# power.net
KiCad netlist of a schematic drawn in Altium Designer
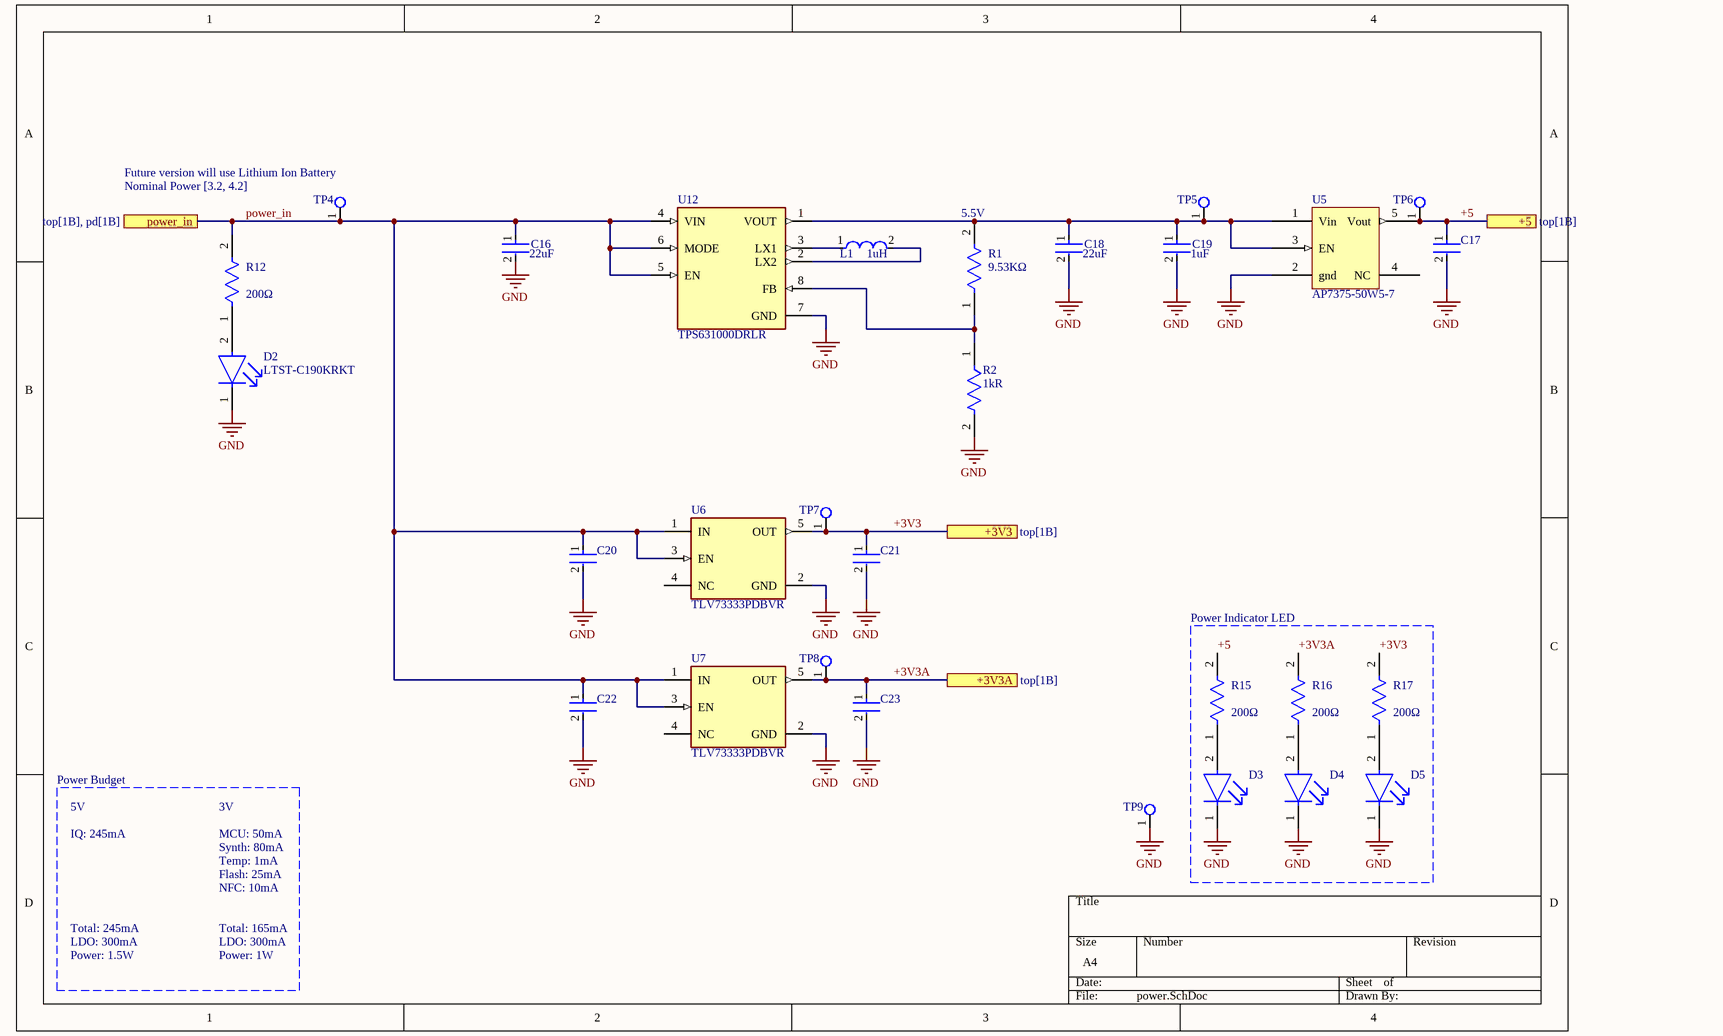
[diagram p0: power.SchDoc]

(export (version "E")
  (design (tool "Eeschema 10.0.6"))
  (components
    (comp (ref "C16")
      (value "GRM188R61A226ME15D")
      (footprint "FP-GRM188-0_2-IPC_C")
      (description "Chip Multilayer Ceramic Capacitors for General Purpose, 0603, 22uF, X5R, 15%, 20%, 10V")
      (fields (field (name "TOLERANCE") "20%") (field (name "CAPACITANCE") "22uF"))
      (libsource (lib "Altium Content Vault") (part "11868f565c42a9108669ba33697ecf6"))
    )
    (comp (ref "C17")
      (value "GRM155R61A106ME11D")
      (footprint "FP-GRM155-0_2-IPC_A")
      (description "Chip Multilayer Ceramic Capacitors for General Purpose, 0402, 10uF, X5R, 15%, 20%, 10V")
      (libsource (lib "Altium Content Vault") (part "b4654b650e69147ec39a6b967a45e02"))
    )
    (comp (ref "C18")
      (value "GRM188R61A226ME15D")
      (footprint "FP-GRM188-0_2-IPC_C")
      (description "Chip Multilayer Ceramic Capacitors for General Purpose, 0603, 22uF, X5R, 15%, 20%, 10V")
      (fields (field (name "TOLERANCE") "20%") (field (name "CAPACITANCE") "22uF"))
      (libsource (lib "Altium Content Vault") (part "11868f565c42a9108669ba33697ecf6"))
    )
    (comp (ref "C19")
      (value "CL10B105KP8NNNC")
      (footprint "FP-CL10-IPC_C")
      (description "Cap Ceramic 1uF 10V X7R ±10% Pad SMD 0603 +125°C T/R")
      (fields (field (name "CAPACITANCE") "1uF") (field (name "TOLERANCE") "10%"))
      (libsource (lib "Altium Content Vault") (part "b4654b650e69147ec39a6b967a45e02"))
    )
    (comp (ref "C20")
      (value "GRM155R61A106ME11D")
      (footprint "FP-GRM155-0_2-IPC_A")
      (description "Chip Multilayer Ceramic Capacitors for General Purpose, 0402, 10uF, X5R, 15%, 20%, 10V")
      (libsource (lib "Altium Content Vault") (part "b4654b650e69147ec39a6b967a45e02"))
    )
    (comp (ref "C21")
      (value "GRM155R61A106ME11D")
      (footprint "FP-GRM155-0_2-IPC_A")
      (description "Chip Multilayer Ceramic Capacitors for General Purpose, 0402, 10uF, X5R, 15%, 20%, 10V")
      (libsource (lib "Altium Content Vault") (part "b4654b650e69147ec39a6b967a45e02"))
    )
    (comp (ref "C22")
      (value "GRM155R61A106ME11D")
      (footprint "FP-GRM155-0_2-IPC_A")
      (description "Chip Multilayer Ceramic Capacitors for General Purpose, 0402, 10uF, X5R, 15%, 20%, 10V")
      (libsource (lib "Altium Content Vault") (part "b4654b650e69147ec39a6b967a45e02"))
    )
    (comp (ref "C23")
      (value "GRM155R61A106ME11D")
      (footprint "FP-GRM155-0_2-IPC_A")
      (description "Chip Multilayer Ceramic Capacitors for General Purpose, 0402, 10uF, X5R, 15%, 20%, 10V")
      (libsource (lib "Altium Content Vault") (part "b4654b650e69147ec39a6b967a45e02"))
    )
    (comp (ref "D2")
      (value "LTST-C190KRKT")
      (footprint "FP-LTST-C190KRKT-MFG")
      (description "LED RED CLEAR CHIP SMD")
      (libsource (lib "Altium Content Vault") (part "8706943c75ba83719d021d2fdc84c58"))
    )
    (comp (ref "D3")
      (value "LTST-C190KRKT")
      (footprint "FP-LTST-C190KRKT-MFG")
      (description "LED RED CLEAR CHIP SMD")
      (libsource (lib "Altium Content Vault") (part "8706943c75ba83719d021d2fdc84c58"))
    )
    (comp (ref "D4")
      (value "LTST-C190KRKT")
      (footprint "FP-LTST-C190KRKT-MFG")
      (description "LED RED CLEAR CHIP SMD")
      (libsource (lib "Altium Content Vault") (part "8706943c75ba83719d021d2fdc84c58"))
    )
    (comp (ref "D5")
      (value "LTST-C190KRKT")
      (footprint "FP-LTST-C190KRKT-MFG")
      (description "LED RED CLEAR CHIP SMD")
      (libsource (lib "Altium Content Vault") (part "8706943c75ba83719d021d2fdc84c58"))
    )
    (comp (ref "L1")
      (value "LQM21PN1R0NGRD")
      (footprint "FP-LQM21PH_G0-IPC_C")
      (description "Multilayer Type Inductor for Power Lines, 0805 (2012), 1μH, 30%, 0.0825Ω, 1.3A")
      (fields (field (name "INDUCTANCE") "1uH") (field (name "TOLERANCE") "30%"))
      (libsource (lib "Altium Content Vault") (part "725321dda6339637d4d059423bc1c3c"))
    )
    (comp (ref "R1")
      (value "9.53KΩ")
      (footprint "FP-RT0603-MFG")
      (description "RES SMD 9.53K OHM 0.1% 1/10W")
      (fields
        (field (name "OCTOPART") "https://octopart.com/rt0603brd079k53l-yageo-1387406")
        (field (name "TOLERANCE") "0.001")
      )
      (libsource (lib "Altium Content Vault") (part "1029c3af85768c4190bb7ad29bc67b5"))
    )
    (comp (ref "R2")
      (value "RC0603FR-071KL")
      (footprint "FP-RC0603-0_55-IPC_C")
      (description "RES 1K OHM 1% 1/10W 0603")
      (fields (field (name "RESISTANCE") "1kR") (field (name "TOLERANCE") "1%"))
      (libsource (lib "Altium Content Vault") (part "1029c3af85768c4190bb7ad29bc67b5"))
    )
    (comp (ref "R12")
      (value "200Ω")
      (footprint "FP-RT0402-MFG")
      (description "RES SMD 200 OHM 0.1% 1/16W 0402")
      (fields (field (name "TOLERANCE") "0.001") (field (name "MANUFACTURER PART NUMBER") "RT0402BRD07200RL"))
      (libsource (lib "Altium Content Vault") (part "1029c3af85768c4190bb7ad29bc67b5"))
    )
    (comp (ref "R15")
      (value "200Ω")
      (footprint "FP-RT0402-MFG")
      (description "RES SMD 200 OHM 0.1% 1/16W 0402")
      (fields (field (name "TOLERANCE") "0.001") (field (name "MANUFACTURER PART NUMBER") "RT0402BRD07200RL"))
      (libsource (lib "Altium Content Vault") (part "1029c3af85768c4190bb7ad29bc67b5"))
    )
    (comp (ref "R16")
      (value "200Ω")
      (footprint "FP-RT0402-MFG")
      (description "RES SMD 200 OHM 0.1% 1/16W 0402")
      (fields (field (name "TOLERANCE") "0.001") (field (name "MANUFACTURER PART NUMBER") "RT0402BRD07200RL"))
      (libsource (lib "Altium Content Vault") (part "1029c3af85768c4190bb7ad29bc67b5"))
    )
    (comp (ref "R17")
      (value "200Ω")
      (footprint "FP-RT0402-MFG")
      (description "RES SMD 200 OHM 0.1% 1/16W 0402")
      (fields (field (name "TOLERANCE") "0.001") (field (name "MANUFACTURER PART NUMBER") "RT0402BRD07200RL"))
      (libsource (lib "Altium Content Vault") (part "1029c3af85768c4190bb7ad29bc67b5"))
    )
    (comp (ref "TP4")
      (value "Test Point")
      (footprint "test_point")
      (libsource (lib "fydp") (part "Test Point"))
    )
    (comp (ref "TP5")
      (value "Test Point")
      (footprint "test_point")
      (libsource (lib "fydp") (part "Test Point"))
    )
    (comp (ref "TP6")
      (value "Test Point")
      (footprint "test_point")
      (libsource (lib "fydp") (part "Test Point"))
    )
    (comp (ref "TP7")
      (value "Test Point")
      (footprint "test_point")
      (libsource (lib "fydp") (part "Test Point"))
    )
    (comp (ref "TP8")
      (value "Test Point")
      (footprint "test_point")
      (libsource (lib "fydp") (part "Test Point"))
    )
    (comp (ref "TP9")
      (value "Test Point")
      (footprint "test_point")
      (libsource (lib "fydp") (part "Test Point"))
    )
    (comp (ref "U5")
      (value "AP7375-50W5-7")
      (footprint "DIODES SOT25")
      (libsource (lib "fydp") (part "AP7375-50W5-7"))
    )
    (comp (ref "U6")
      (value "TLV73333PDBVR")
      (footprint "FP-DBV0005A-MFG")
      (description "IC REG LINEAR 3.3V 300MA SOT23-5")
      (fields
        (field (name "MANUFACTURER") "Texas Instruments")
        (field (name "OCTOPART") "https://octopart.com/tlv73333pdbvr-texas+instruments-51080890")
      )
      (libsource (lib "Altium Content Vault") (part "10cdd6a861ce8db355dac0efc8b397e"))
    )
    (comp (ref "U7")
      (value "TLV73333PDBVR")
      (footprint "FP-DBV0005A-MFG")
      (description "IC REG LINEAR 3.3V 300MA SOT23-5")
      (fields
        (field (name "MANUFACTURER") "Texas Instruments")
        (field (name "OCTOPART") "https://octopart.com/tlv73333pdbvr-texas+instruments-51080890")
      )
      (libsource (lib "Altium Content Vault") (part "10cdd6a861ce8db355dac0efc8b397e"))
    )
    (comp (ref "U12")
      (value "TPS631000DRLR")
      (footprint "SOT50P160X60-8N")
      (libsource (lib "fydp") (part "TPS631000DRLR"))
    )
  )
  (nets
    (net (code "1") (name "/+3V3") (class "Default")
      (node (ref "C21") (pin "1") (pinfunction "1_1") (pintype "passive"))
      (node (ref "R17") (pin "2") (pinfunction "2_2") (pintype "passive"))
      (node (ref "TP7") (pin "1") (pintype "passive"))
      (node (ref "U6") (pin "5") (pinfunction "OUT_5") (pintype "output"))
    )
    (net (code "2") (name "/+3V3A") (class "Default")
      (node (ref "C23") (pin "1") (pinfunction "1_1") (pintype "passive"))
      (node (ref "R16") (pin "2") (pinfunction "2_2") (pintype "passive"))
      (node (ref "TP8") (pin "1") (pintype "passive"))
      (node (ref "U7") (pin "5") (pinfunction "OUT_5") (pintype "output"))
    )
    (net (code "3") (name "/+5") (class "Default")
      (node (ref "C17") (pin "1") (pinfunction "1_1") (pintype "passive"))
      (node (ref "R15") (pin "2") (pinfunction "2_2") (pintype "passive"))
      (node (ref "TP6") (pin "1") (pintype "passive"))
      (node (ref "U5") (pin "5") (pinfunction "Vout_5") (pintype "output"))
    )
    (net (code "4") (name "/power_in") (class "Default")
      (node (ref "C16") (pin "1") (pinfunction "1_1") (pintype "passive"))
      (node (ref "C20") (pin "1") (pinfunction "1_1") (pintype "passive"))
      (node (ref "C22") (pin "1") (pinfunction "1_1") (pintype "passive"))
      (node (ref "R12") (pin "2") (pinfunction "2_2") (pintype "passive"))
      (node (ref "TP4") (pin "1") (pintype "passive"))
      (node (ref "U12") (pin "4") (pinfunction "VIN_4") (pintype "input"))
      (node (ref "U12") (pin "5") (pinfunction "EN_5") (pintype "input"))
      (node (ref "U12") (pin "6") (pinfunction "MODE_6") (pintype "input"))
      (node (ref "U6") (pin "1") (pinfunction "IN_1") (pintype "power_in"))
      (node (ref "U6") (pin "3") (pinfunction "EN_3") (pintype "input"))
      (node (ref "U7") (pin "1") (pinfunction "IN_1") (pintype "power_in"))
      (node (ref "U7") (pin "3") (pinfunction "EN_3") (pintype "input"))
    )
    (net (code "5") (name "GND") (class "Default")
      (node (ref "C16") (pin "2") (pinfunction "2_2") (pintype "passive"))
      (node (ref "C17") (pin "2") (pinfunction "2_2") (pintype "passive"))
      (node (ref "C18") (pin "2") (pinfunction "2_2") (pintype "passive"))
      (node (ref "C19") (pin "2") (pinfunction "2_2") (pintype "passive"))
      (node (ref "C20") (pin "2") (pinfunction "2_2") (pintype "passive"))
      (node (ref "C21") (pin "2") (pinfunction "2_2") (pintype "passive"))
      (node (ref "C22") (pin "2") (pinfunction "2_2") (pintype "passive"))
      (node (ref "C23") (pin "2") (pinfunction "2_2") (pintype "passive"))
      (node (ref "D2") (pin "1") (pinfunction "C_1") (pintype "passive"))
      (node (ref "D3") (pin "1") (pinfunction "C_1") (pintype "passive"))
      (node (ref "D4") (pin "1") (pinfunction "C_1") (pintype "passive"))
      (node (ref "D5") (pin "1") (pinfunction "C_1") (pintype "passive"))
      (node (ref "R2") (pin "2") (pinfunction "2_2") (pintype "passive"))
      (node (ref "TP9") (pin "1") (pintype "passive"))
      (node (ref "U12") (pin "7") (pinfunction "GND_7") (pintype "power_in"))
      (node (ref "U5") (pin "2") (pinfunction "gnd_2") (pintype "power_in"))
      (node (ref "U6") (pin "2") (pinfunction "GND_2") (pintype "power_in"))
      (node (ref "U7") (pin "2") (pinfunction "GND_2") (pintype "power_in"))
    )
    (net (code "6") (name "Net-(D2-A)") (class "Default")
      (node (ref "D2") (pin "2") (pinfunction "A_2") (pintype "passive"))
      (node (ref "R12") (pin "1") (pinfunction "1_1") (pintype "passive"))
    )
    (net (code "7") (name "Net-(D3-A)") (class "Default")
      (node (ref "D3") (pin "2") (pinfunction "A_2") (pintype "passive"))
      (node (ref "R15") (pin "1") (pinfunction "1_1") (pintype "passive"))
    )
    (net (code "8") (name "Net-(D4-A)") (class "Default")
      (node (ref "D4") (pin "2") (pinfunction "A_2") (pintype "passive"))
      (node (ref "R16") (pin "1") (pinfunction "1_1") (pintype "passive"))
    )
    (net (code "9") (name "Net-(D5-A)") (class "Default")
      (node (ref "D5") (pin "2") (pinfunction "A_2") (pintype "passive"))
      (node (ref "R17") (pin "1") (pinfunction "1_1") (pintype "passive"))
    )
    (net (code "10") (name "Net-(U12-FB)") (class "Default")
      (node (ref "R1") (pin "1") (pinfunction "1_1") (pintype "passive"))
      (node (ref "R2") (pin "1") (pinfunction "1_1") (pintype "passive"))
      (node (ref "U12") (pin "8") (pinfunction "FB_8") (pintype "input"))
    )
    (net (code "11") (name "Net-(U12-LX1)") (class "Default")
      (node (ref "L1") (pin "1") (pinfunction "1_1") (pintype "passive"))
      (node (ref "U12") (pin "3") (pinfunction "LX1_3") (pintype "output"))
    )
    (net (code "12") (name "Net-(U12-LX2)") (class "Default")
      (node (ref "L1") (pin "2") (pinfunction "2_2") (pintype "passive"))
      (node (ref "U12") (pin "2") (pinfunction "LX2_2") (pintype "output"))
    )
    (net (code "13") (name "Net-(U12-VOUT)") (class "Default")
      (node (ref "C18") (pin "1") (pinfunction "1_1") (pintype "passive"))
      (node (ref "C19") (pin "1") (pinfunction "1_1") (pintype "passive"))
      (node (ref "R1") (pin "2") (pinfunction "2_2") (pintype "passive"))
      (node (ref "TP5") (pin "1") (pintype "passive"))
      (node (ref "U12") (pin "1") (pinfunction "VOUT_1") (pintype "output"))
      (node (ref "U5") (pin "1") (pinfunction "Vin_1") (pintype "power_in"))
      (node (ref "U5") (pin "3") (pinfunction "EN_3") (pintype "input"))
    )
    (net (code "14") (name "unconnected-(U5-NC-Pad4)") (class "Default")
      (node (ref "U5") (pin "4") (pinfunction "NC_4") (pintype "passive"))
    )
    (net (code "15") (name "unconnected-(U6-NC-Pad4)") (class "Default")
      (node (ref "U6") (pin "4") (pinfunction "NC_4") (pintype "passive"))
    )
    (net (code "16") (name "unconnected-(U7-NC-Pad4)") (class "Default")
      (node (ref "U7") (pin "4") (pinfunction "NC_4") (pintype "passive"))
    )
  )
)
